# Grownetics_MUX_Shield.net
KiCad netlist of a schematic drawn in EAGLE
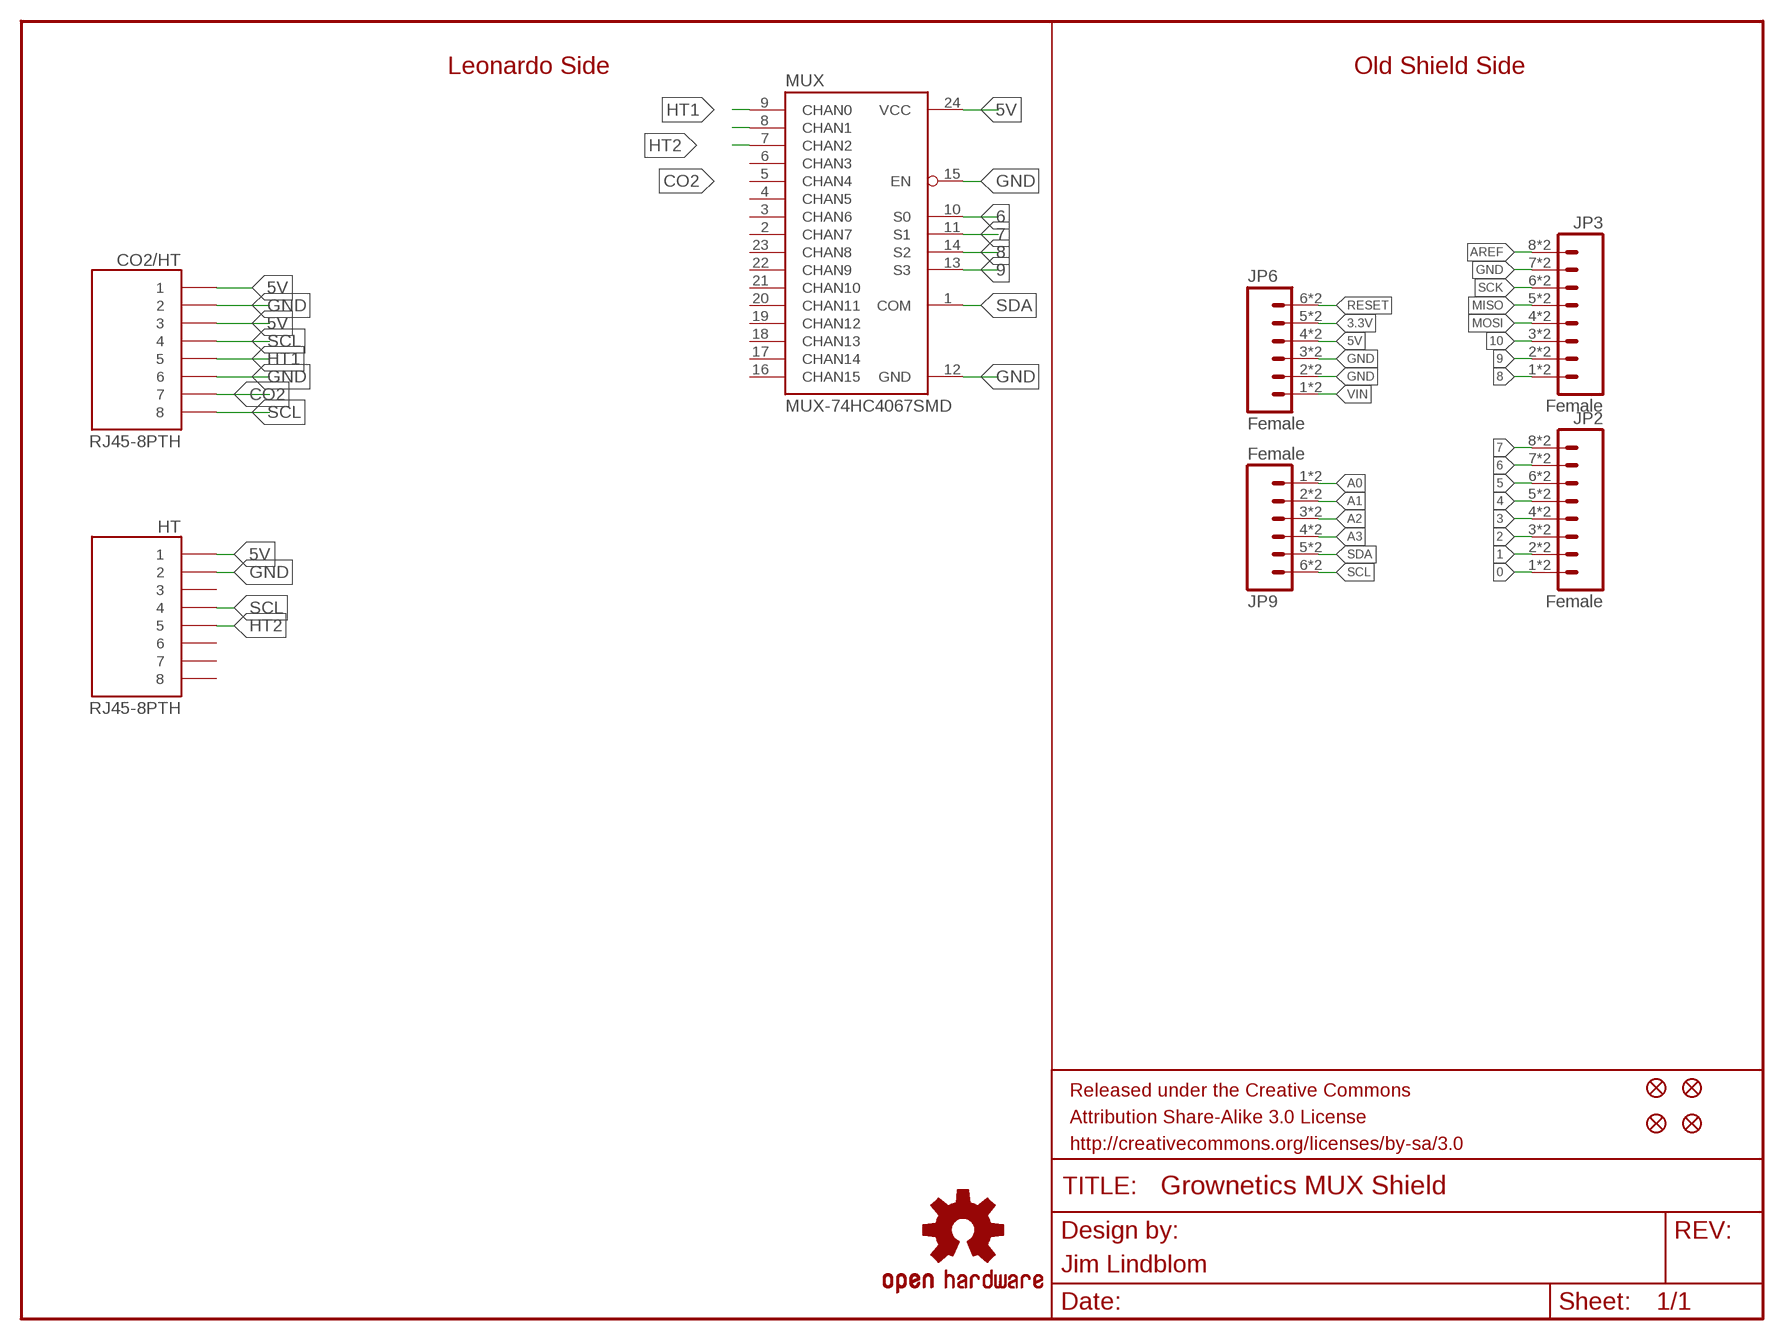
[diagram p0: schematic, sheet 1]

(export (version "E")
  (design (tool "Eeschema 10.0.6"))
  (components
    (comp (ref "CO2/HT")
      (value "RJ45-8PTH")
      (footprint "eagle-import:RJ45-8")
      (libsource (lib "eagle-import") (part "RJ45-8PTH"))
    )
    (comp (ref "HT")
      (value "RJ45-8PTH")
      (footprint "eagle-import:RJ45-8")
      (libsource (lib "eagle-import") (part "RJ45-8PTH"))
    )
    (comp (ref "JP2")
      (value "Female")
      (footprint "eagle-import:1X08_SMD_COMBINED")
      (libsource (lib "eagle-import") (part "M08SMD-COMBO"))
    )
    (comp (ref "JP3")
      (value "Female")
      (footprint "eagle-import:1X08_SMD_COMBINED")
      (libsource (lib "eagle-import") (part "M08SMD-COMBO"))
    )
    (comp (ref "JP6")
      (value "Female")
      (footprint "eagle-import:1X06_SMD_STRAIGHT_COMBO")
      (libsource (lib "eagle-import") (part "M06SMD-STRAIGHT-COMBO"))
    )
    (comp (ref "JP9")
      (value "Female")
      (footprint "eagle-import:1X06_SMD_STRAIGHT_COMBO")
      (libsource (lib "eagle-import") (part "M06SMD-STRAIGHT-COMBO"))
    )
    (comp (ref "JP11")
      (value "FIDUCIALUFIDUCIAL")
      (footprint "eagle-import:MICRO-FIDUCIAL")
      (libsource (lib "eagle-import") (part "FIDUCIALUFIDUCIAL"))
    )
    (comp (ref "JP12")
      (value "FIDUCIALUFIDUCIAL")
      (footprint "eagle-import:MICRO-FIDUCIAL")
      (libsource (lib "eagle-import") (part "FIDUCIALUFIDUCIAL"))
    )
    (comp (ref "JP13")
      (value "FIDUCIALUFIDUCIAL")
      (footprint "eagle-import:MICRO-FIDUCIAL")
      (libsource (lib "eagle-import") (part "FIDUCIALUFIDUCIAL"))
    )
    (comp (ref "JP14")
      (value "FIDUCIALUFIDUCIAL")
      (footprint "eagle-import:MICRO-FIDUCIAL")
      (libsource (lib "eagle-import") (part "FIDUCIALUFIDUCIAL"))
    )
    (comp (ref "MUX")
      (value "MUX-74HC4067SMD")
      (footprint "eagle-import:SSOP24")
      (libsource (lib "eagle-import") (part "MUX-74HC4067SMD"))
    )
    (comp (ref "U$1")
      (value "OSHW-LOGOS")
      (footprint "eagle-import:OSHW-LOGO-S")
      (libsource (lib "eagle-import") (part "OSHW-LOGOS"))
    )
  )
  (nets
    (net (code "1") (name "0") (class "Default")
      (node (ref "JP2") (pin "1") (pinfunction "1_1") (pintype "passive"))
      (node (ref "JP2") (pin "1@2") (pinfunction "1_1@2") (pintype "passive"))
    )
    (net (code "2") (name "1") (class "Default")
      (node (ref "JP2") (pin "2") (pinfunction "2_2") (pintype "passive"))
      (node (ref "JP2") (pin "2@2") (pinfunction "2_2@2") (pintype "passive"))
    )
    (net (code "3") (name "2") (class "Default")
      (node (ref "JP2") (pin "3") (pinfunction "3_3") (pintype "passive"))
      (node (ref "JP2") (pin "3@2") (pinfunction "3_3@2") (pintype "passive"))
    )
    (net (code "4") (name "3") (class "Default")
      (node (ref "JP2") (pin "4") (pinfunction "4_4") (pintype "passive"))
      (node (ref "JP2") (pin "4@2") (pinfunction "4_4@2") (pintype "passive"))
    )
    (net (code "5") (name "3.3V") (class "Default")
      (node (ref "JP6") (pin "5") (pinfunction "5_5") (pintype "passive"))
      (node (ref "JP6") (pin "5-2") (pinfunction "5_5-2") (pintype "passive"))
    )
    (net (code "6") (name "4") (class "Default")
      (node (ref "JP2") (pin "5") (pinfunction "5_5") (pintype "passive"))
      (node (ref "JP2") (pin "5@2") (pinfunction "5_5@2") (pintype "passive"))
    )
    (net (code "7") (name "5") (class "Default")
      (node (ref "JP2") (pin "6") (pinfunction "6_6") (pintype "passive"))
      (node (ref "JP2") (pin "6@2") (pinfunction "6_6@2") (pintype "passive"))
    )
    (net (code "8") (name "5V") (class "Default")
      (node (ref "CO2/HT") (pin "1") (pinfunction "1_1") (pintype "bidirectional"))
      (node (ref "CO2/HT") (pin "3") (pinfunction "3_3") (pintype "bidirectional"))
      (node (ref "HT") (pin "1") (pinfunction "1_1") (pintype "bidirectional"))
      (node (ref "JP6") (pin "4") (pinfunction "4_4") (pintype "passive"))
      (node (ref "JP6") (pin "4-2") (pinfunction "4_4-2") (pintype "passive"))
      (node (ref "MUX") (pin "24") (pinfunction "VCC_24") (pintype "bidirectional"))
    )
    (net (code "9") (name "6") (class "Default")
      (node (ref "JP2") (pin "7") (pinfunction "7_7") (pintype "passive"))
      (node (ref "JP2") (pin "7@2") (pinfunction "7_7@2") (pintype "passive"))
      (node (ref "MUX") (pin "10") (pinfunction "S0_10") (pintype "input"))
    )
    (net (code "10") (name "7") (class "Default")
      (node (ref "JP2") (pin "8") (pinfunction "8_8") (pintype "passive"))
      (node (ref "JP2") (pin "8@2") (pinfunction "8_8@2") (pintype "passive"))
      (node (ref "MUX") (pin "11") (pinfunction "S1_11") (pintype "input"))
    )
    (net (code "11") (name "8") (class "Default")
      (node (ref "JP3") (pin "1") (pinfunction "1_1") (pintype "passive"))
      (node (ref "JP3") (pin "1@2") (pinfunction "1_1@2") (pintype "passive"))
      (node (ref "MUX") (pin "14") (pinfunction "S2_14") (pintype "input"))
    )
    (net (code "12") (name "9") (class "Default")
      (node (ref "JP3") (pin "2") (pinfunction "2_2") (pintype "passive"))
      (node (ref "JP3") (pin "2@2") (pinfunction "2_2@2") (pintype "passive"))
      (node (ref "MUX") (pin "13") (pinfunction "S3_13") (pintype "input"))
    )
    (net (code "13") (name "10") (class "Default")
      (node (ref "JP3") (pin "3") (pinfunction "3_3") (pintype "passive"))
      (node (ref "JP3") (pin "3@2") (pinfunction "3_3@2") (pintype "passive"))
    )
    (net (code "14") (name "A0") (class "Default")
      (node (ref "JP9") (pin "1") (pinfunction "1_1") (pintype "passive"))
      (node (ref "JP9") (pin "1-2") (pinfunction "1_1-2") (pintype "passive"))
    )
    (net (code "15") (name "A1") (class "Default")
      (node (ref "JP9") (pin "2") (pinfunction "2_2") (pintype "passive"))
      (node (ref "JP9") (pin "2-2") (pinfunction "2_2-2") (pintype "passive"))
    )
    (net (code "16") (name "A2") (class "Default")
      (node (ref "JP9") (pin "3") (pinfunction "3_3") (pintype "passive"))
      (node (ref "JP9") (pin "3-2") (pinfunction "3_3-2") (pintype "passive"))
    )
    (net (code "17") (name "A3") (class "Default")
      (node (ref "JP9") (pin "4") (pinfunction "4_4") (pintype "passive"))
      (node (ref "JP9") (pin "4-2") (pinfunction "4_4-2") (pintype "passive"))
    )
    (net (code "18") (name "AREF") (class "Default")
      (node (ref "JP3") (pin "8") (pinfunction "8_8") (pintype "passive"))
      (node (ref "JP3") (pin "8@2") (pinfunction "8_8@2") (pintype "passive"))
    )
    (net (code "19") (name "CO2") (class "Default")
      (node (ref "CO2/HT") (pin "7") (pinfunction "7_7") (pintype "bidirectional"))
      (node (ref "MUX") (pin "7") (pinfunction "CHAN2_7") (pintype "bidirectional"))
    )
    (net (code "20") (name "GND") (class "Default")
      (node (ref "CO2/HT") (pin "2") (pinfunction "2_2") (pintype "bidirectional"))
      (node (ref "CO2/HT") (pin "6") (pinfunction "6_6") (pintype "bidirectional"))
      (node (ref "HT") (pin "2") (pinfunction "2_2") (pintype "bidirectional"))
      (node (ref "JP3") (pin "7") (pinfunction "7_7") (pintype "passive"))
      (node (ref "JP3") (pin "7@2") (pinfunction "7_7@2") (pintype "passive"))
      (node (ref "JP6") (pin "2") (pinfunction "2_2") (pintype "passive"))
      (node (ref "JP6") (pin "2-2") (pinfunction "2_2-2") (pintype "passive"))
      (node (ref "JP6") (pin "3") (pinfunction "3_3") (pintype "passive"))
      (node (ref "JP6") (pin "3-2") (pinfunction "3_3-2") (pintype "passive"))
      (node (ref "MUX") (pin "12") (pinfunction "GND_12") (pintype "bidirectional"))
      (node (ref "MUX") (pin "15") (pinfunction "EN_15") (pintype "input"))
    )
    (net (code "21") (name "HT1") (class "Default")
      (node (ref "CO2/HT") (pin "5") (pinfunction "5_5") (pintype "bidirectional"))
      (node (ref "MUX") (pin "9") (pinfunction "CHAN0_9") (pintype "bidirectional"))
    )
    (net (code "22") (name "HT2") (class "Default")
      (node (ref "HT") (pin "5") (pinfunction "5_5") (pintype "bidirectional"))
      (node (ref "MUX") (pin "8") (pinfunction "CHAN1_8") (pintype "bidirectional"))
    )
    (net (code "23") (name "MISO") (class "Default")
      (node (ref "JP3") (pin "5") (pinfunction "5_5") (pintype "passive"))
      (node (ref "JP3") (pin "5@2") (pinfunction "5_5@2") (pintype "passive"))
    )
    (net (code "24") (name "MOSI") (class "Default")
      (node (ref "JP3") (pin "4") (pinfunction "4_4") (pintype "passive"))
      (node (ref "JP3") (pin "4@2") (pinfunction "4_4@2") (pintype "passive"))
    )
    (net (code "25") (name "RESET") (class "Default")
      (node (ref "JP6") (pin "6") (pinfunction "6_6") (pintype "passive"))
      (node (ref "JP6") (pin "6-2") (pinfunction "6_6-2") (pintype "passive"))
    )
    (net (code "26") (name "SCK") (class "Default")
      (node (ref "JP3") (pin "6") (pinfunction "6_6") (pintype "passive"))
      (node (ref "JP3") (pin "6@2") (pinfunction "6_6@2") (pintype "passive"))
    )
    (net (code "27") (name "SCL") (class "Default")
      (node (ref "CO2/HT") (pin "4") (pinfunction "4_4") (pintype "bidirectional"))
      (node (ref "CO2/HT") (pin "8") (pinfunction "8_8") (pintype "bidirectional"))
      (node (ref "HT") (pin "4") (pinfunction "4_4") (pintype "bidirectional"))
      (node (ref "JP9") (pin "6") (pinfunction "6_6") (pintype "passive"))
      (node (ref "JP9") (pin "6-2") (pinfunction "6_6-2") (pintype "passive"))
    )
    (net (code "28") (name "SDA") (class "Default")
      (node (ref "JP9") (pin "5") (pinfunction "5_5") (pintype "passive"))
      (node (ref "JP9") (pin "5-2") (pinfunction "5_5-2") (pintype "passive"))
      (node (ref "MUX") (pin "1") (pinfunction "COM_1") (pintype "bidirectional"))
    )
    (net (code "29") (name "VIN") (class "Default")
      (node (ref "JP6") (pin "1") (pinfunction "1_1") (pintype "passive"))
      (node (ref "JP6") (pin "1-2") (pinfunction "1_1-2") (pintype "passive"))
    )
    (net (code "30") (name "unconnected-(HT-Pad3)") (class "Default")
      (node (ref "HT") (pin "3") (pinfunction "3_3") (pintype "bidirectional"))
    )
    (net (code "31") (name "unconnected-(HT-Pad6)") (class "Default")
      (node (ref "HT") (pin "6") (pinfunction "6_6") (pintype "bidirectional"))
    )
    (net (code "32") (name "unconnected-(HT-Pad7)") (class "Default")
      (node (ref "HT") (pin "7") (pinfunction "7_7") (pintype "bidirectional"))
    )
    (net (code "33") (name "unconnected-(HT-Pad8)") (class "Default")
      (node (ref "HT") (pin "8") (pinfunction "8_8") (pintype "bidirectional"))
    )
    (net (code "34") (name "unconnected-(MUX-CHAN3-Pad6)") (class "Default")
      (node (ref "MUX") (pin "6") (pinfunction "CHAN3_6") (pintype "bidirectional"))
    )
    (net (code "35") (name "unconnected-(MUX-CHAN4-Pad5)") (class "Default")
      (node (ref "MUX") (pin "5") (pinfunction "CHAN4_5") (pintype "bidirectional"))
    )
    (net (code "36") (name "unconnected-(MUX-CHAN5-Pad4)") (class "Default")
      (node (ref "MUX") (pin "4") (pinfunction "CHAN5_4") (pintype "bidirectional"))
    )
    (net (code "37") (name "unconnected-(MUX-CHAN6-Pad3)") (class "Default")
      (node (ref "MUX") (pin "3") (pinfunction "CHAN6_3") (pintype "bidirectional"))
    )
    (net (code "38") (name "unconnected-(MUX-CHAN7-Pad2)") (class "Default")
      (node (ref "MUX") (pin "2") (pinfunction "CHAN7_2") (pintype "bidirectional"))
    )
    (net (code "39") (name "unconnected-(MUX-CHAN8-Pad23)") (class "Default")
      (node (ref "MUX") (pin "23") (pinfunction "CHAN8_23") (pintype "bidirectional"))
    )
    (net (code "40") (name "unconnected-(MUX-CHAN9-Pad22)") (class "Default")
      (node (ref "MUX") (pin "22") (pinfunction "CHAN9_22") (pintype "bidirectional"))
    )
    (net (code "41") (name "unconnected-(MUX-CHAN10-Pad21)") (class "Default")
      (node (ref "MUX") (pin "21") (pinfunction "CHAN10_21") (pintype "bidirectional"))
    )
    (net (code "42") (name "unconnected-(MUX-CHAN11-Pad20)") (class "Default")
      (node (ref "MUX") (pin "20") (pinfunction "CHAN11_20") (pintype "bidirectional"))
    )
    (net (code "43") (name "unconnected-(MUX-CHAN12-Pad19)") (class "Default")
      (node (ref "MUX") (pin "19") (pinfunction "CHAN12_19") (pintype "bidirectional"))
    )
    (net (code "44") (name "unconnected-(MUX-CHAN13-Pad18)") (class "Default")
      (node (ref "MUX") (pin "18") (pinfunction "CHAN13_18") (pintype "bidirectional"))
    )
    (net (code "45") (name "unconnected-(MUX-CHAN14-Pad17)") (class "Default")
      (node (ref "MUX") (pin "17") (pinfunction "CHAN14_17") (pintype "bidirectional"))
    )
    (net (code "46") (name "unconnected-(MUX-CHAN15-Pad16)") (class "Default")
      (node (ref "MUX") (pin "16") (pinfunction "CHAN15_16") (pintype "bidirectional"))
    )
  )
)
